# Siwa_PCB.net
KiCad netlist of a schematic drawn in Altium Designer
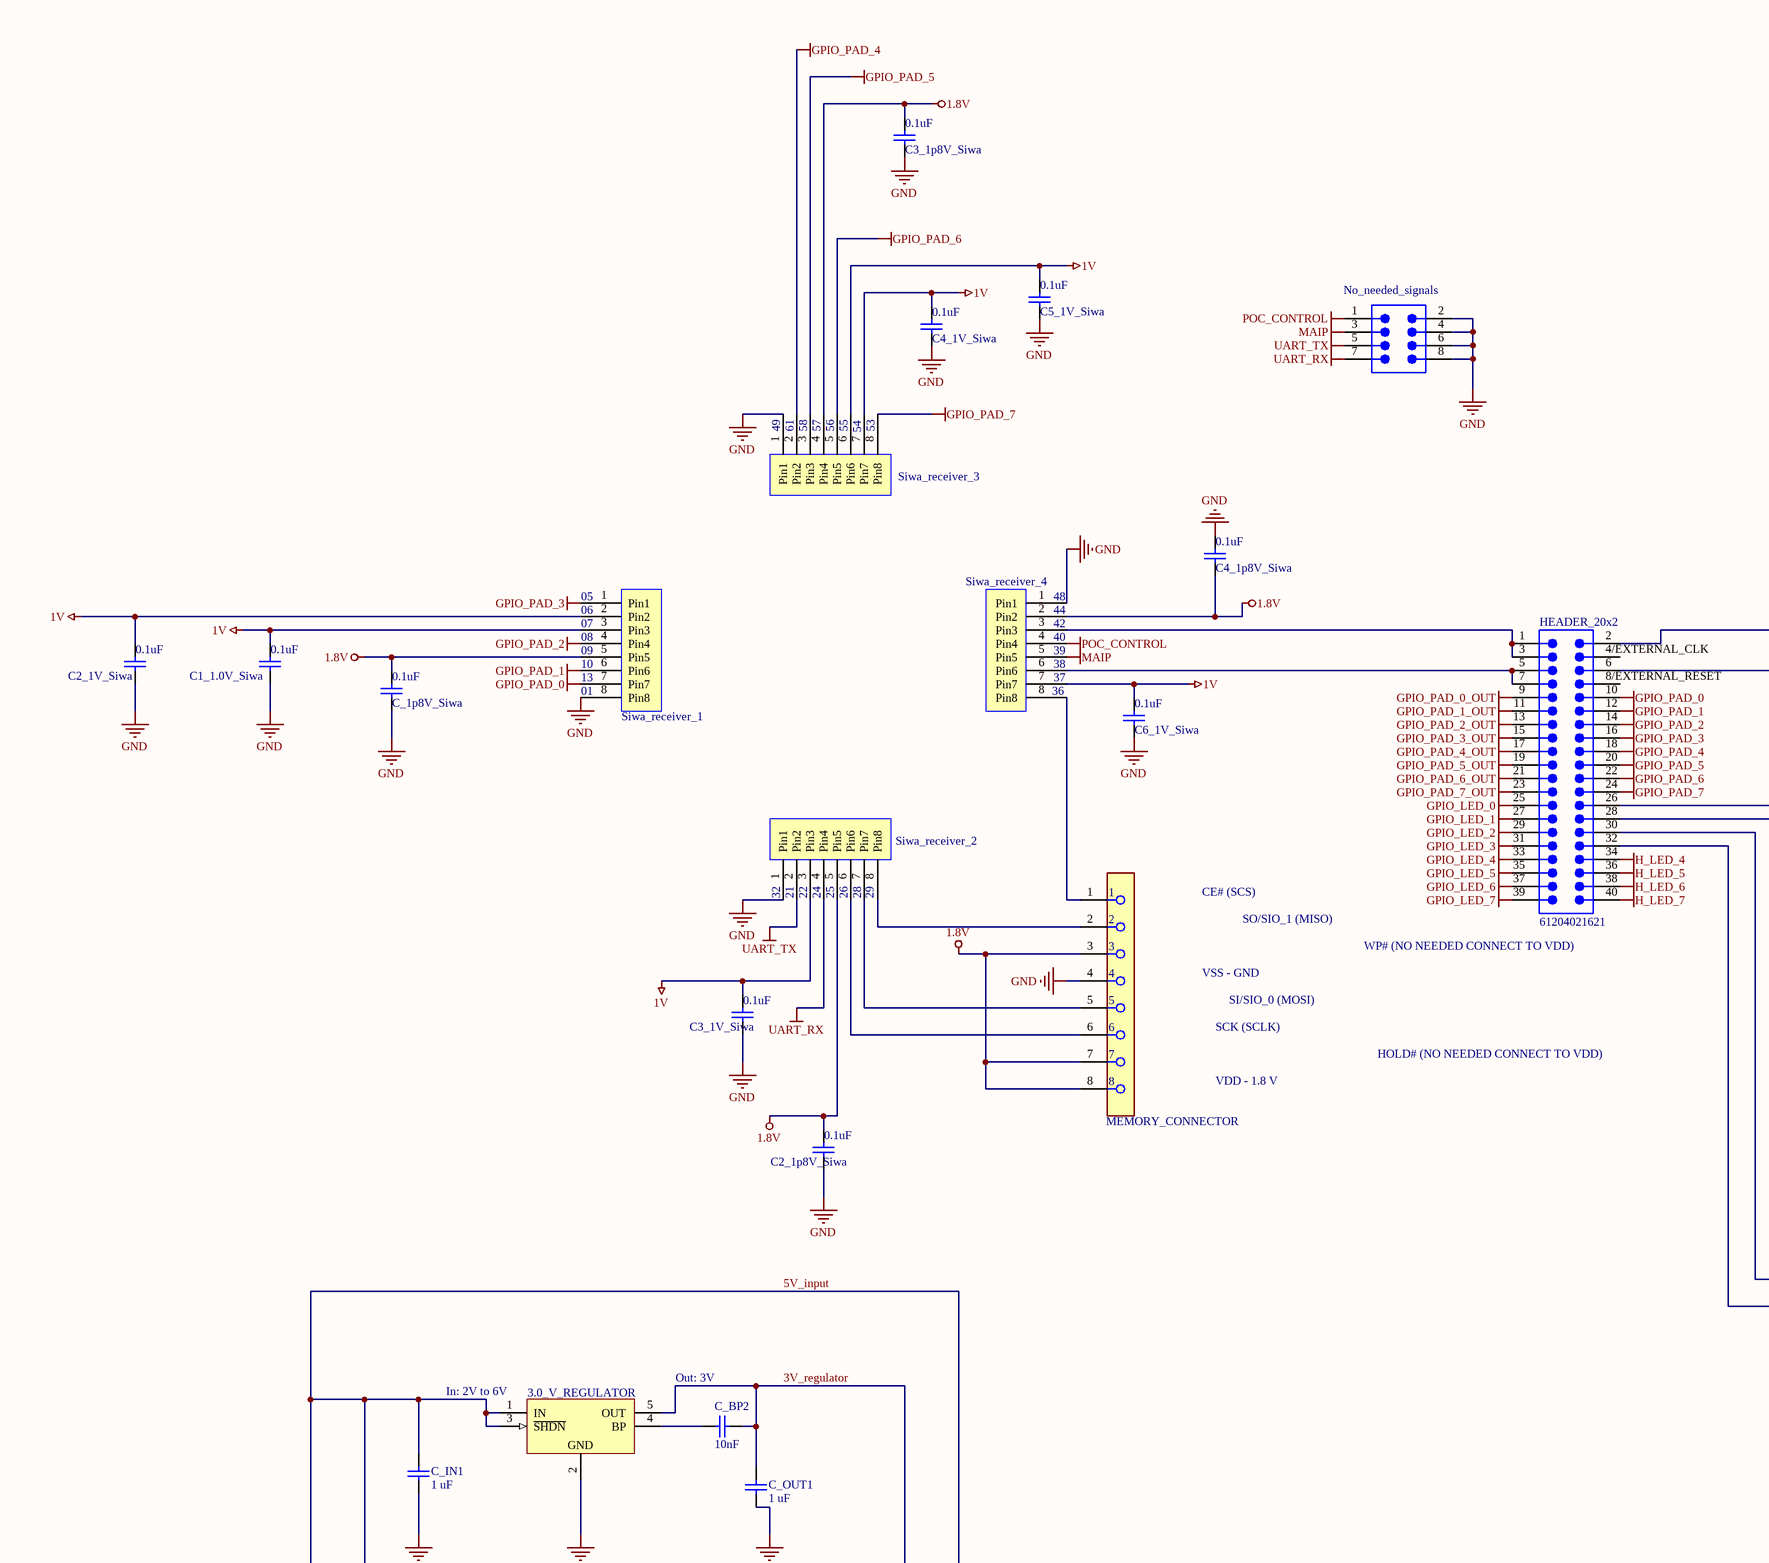
[diagram p0: Siwa_PCB.SchDoc, top left]
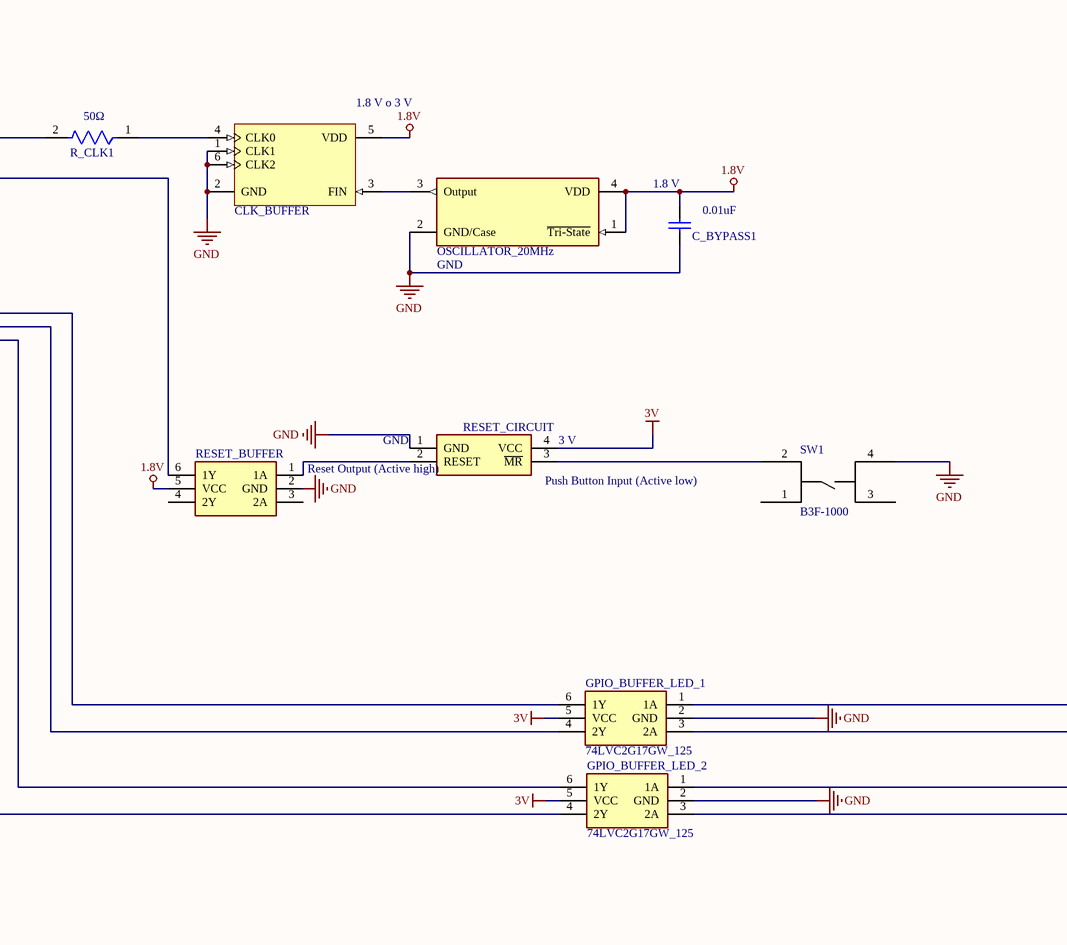
[diagram p1: Siwa_PCB.SchDoc, top right]
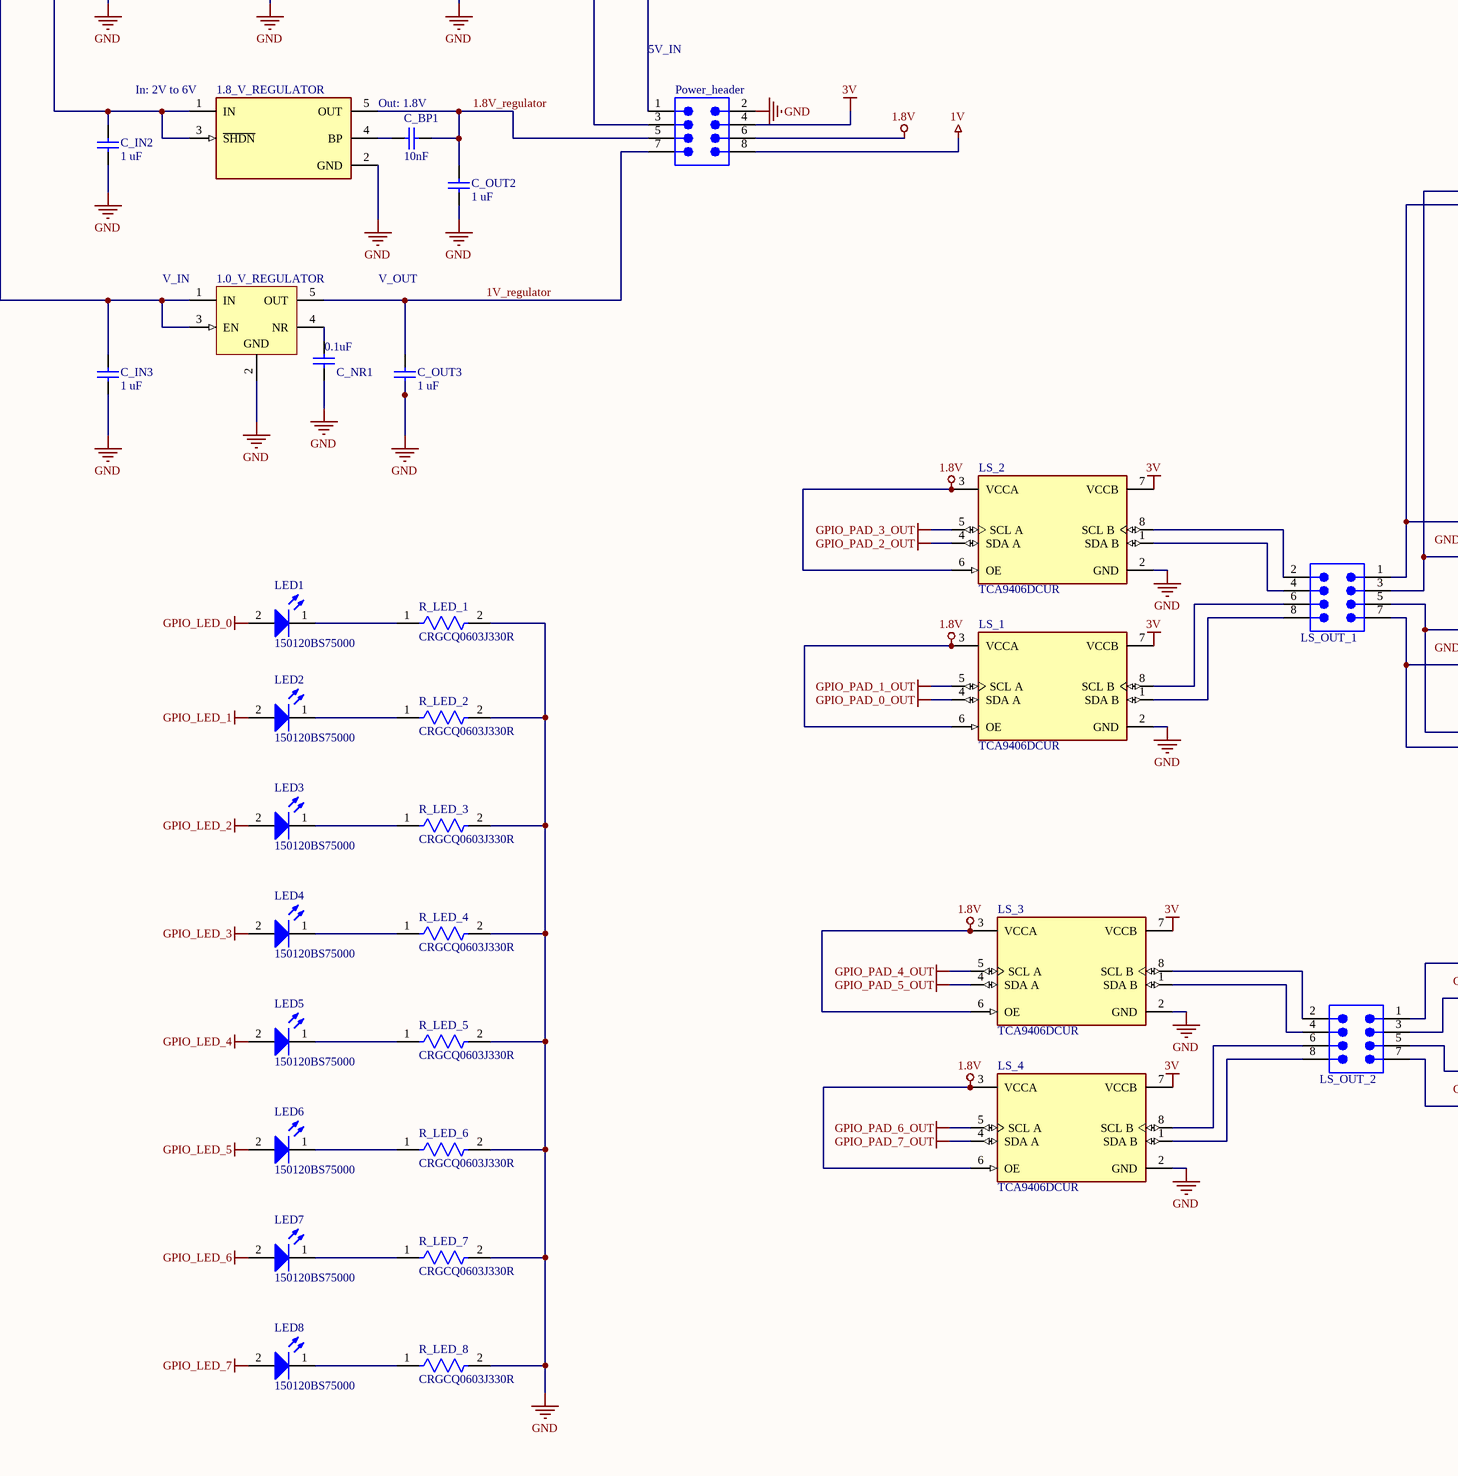
[diagram p2: Siwa_PCB.SchDoc, bottom left]
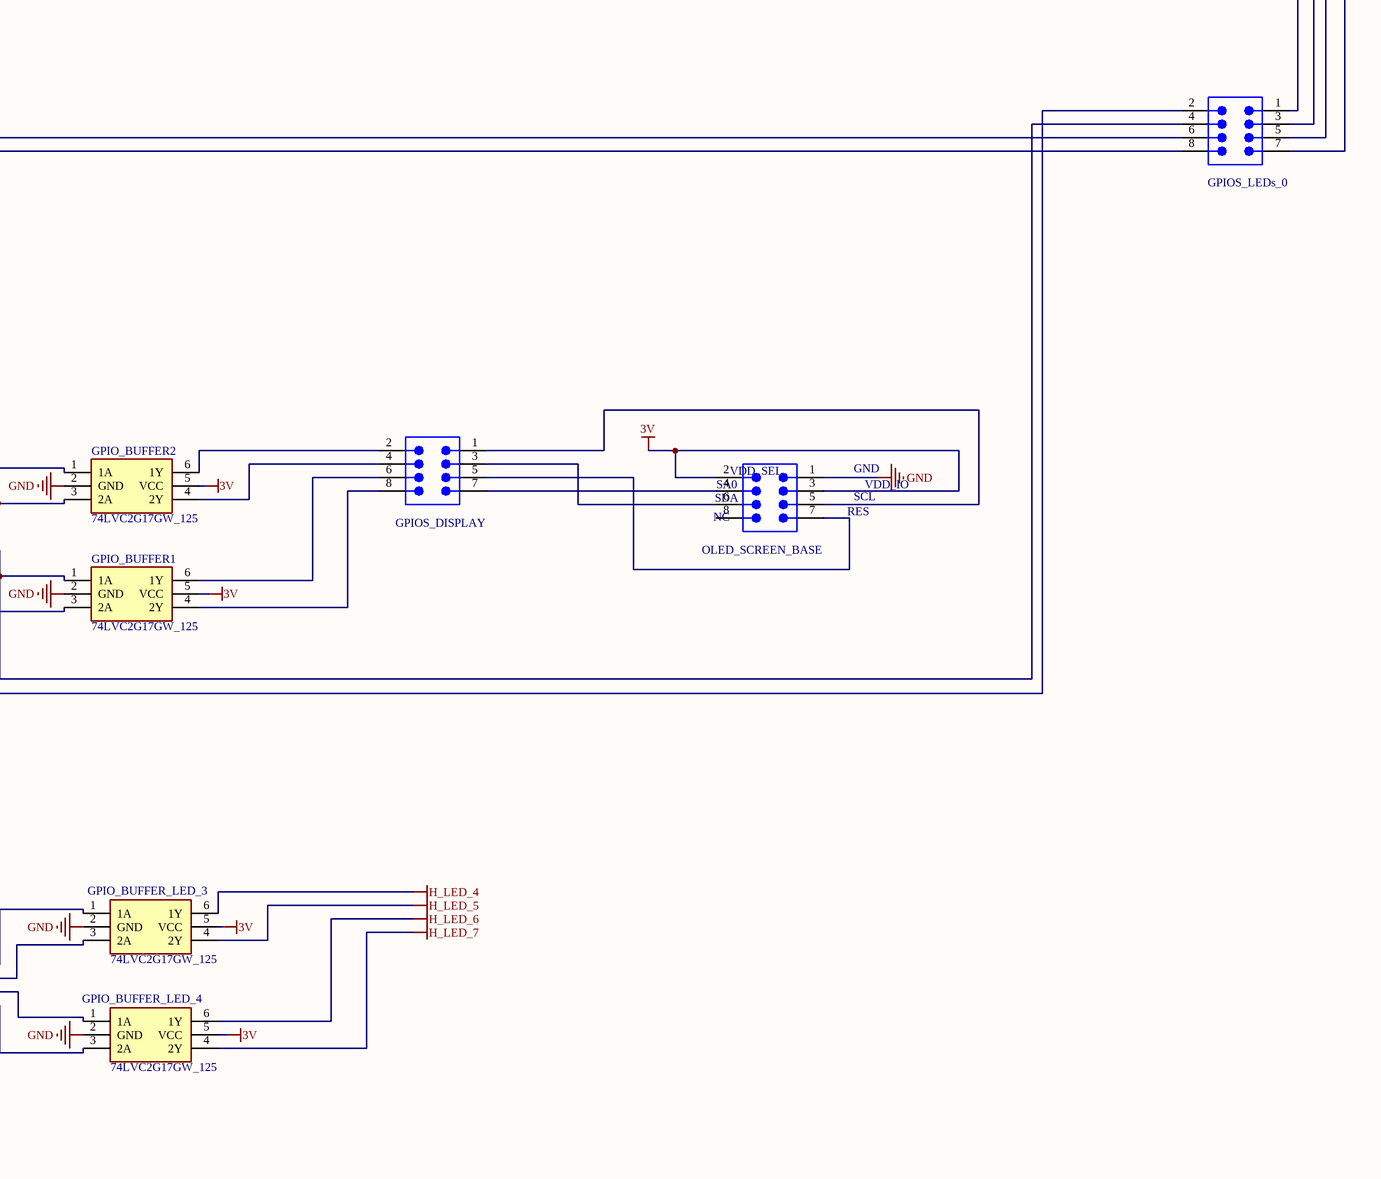
[diagram p3: Siwa_PCB.SchDoc, bottom right]

(export (version "E")
  (design (tool "Eeschema 10.0.6"))
  (components
    (comp (ref "1.0_V_REGULATOR")
      (value "TPS71710DCKT")
      (footprint "DCK0005A_M")
      (fields (field (name "MANUFACTURER") "Texas Instruments"))
      (libsource (lib "Altium Content Vault") (part "TI-TPS79NXX-YYSOT5"))
    )
    (comp (ref "1.8_V_REGULATOR")
      (value "MAX8510EXK18+T")
      (footprint "FP-X5-1-MFG")
      (description "IC REG LINEAR 1.8V 120MA SC70-5")
      (libsource (lib "Altium Content Vault") (part "355d6218c957986cfc1b3588039a240"))
    )
    (comp (ref "3.0_V_REGULATOR")
      (value "MAX8510EXK30+T")
      (footprint "X5-1_N")
      (libsource (lib "Altium Content Vault") (part "MAX-MAX8510-SOT5"))
    )
    (comp (ref "C1_1.0V_Siwa")
      (value "0.1uF")
      (footprint "CAPC1608X92X38NL15T08")
      (fields (field (name "MANUFACTURER") "Vitramon") (field (name "PART NUMBER") "VJ0603Y104KXXAP"))
      (libsource (lib "Altium Content Vault") (part "CAP"))
    )
    (comp (ref "C2_1p8V_Siwa")
      (value "0.1uF")
      (footprint "CAPC1608X92X38NL15T08")
      (fields (field (name "MANUFACTURER") "Vitramon") (field (name "PART NUMBER") "VJ0603Y104KXXAP"))
      (libsource (lib "Altium Content Vault") (part "CAP"))
    )
    (comp (ref "C2_1V_Siwa")
      (value "0.1uF")
      (footprint "CAPC1608X92X38NL15T08")
      (fields (field (name "MANUFACTURER") "Vitramon") (field (name "PART NUMBER") "VJ0603Y104KXXAP"))
      (libsource (lib "Altium Content Vault") (part "CAP"))
    )
    (comp (ref "C3_1p8V_Siwa")
      (value "0.1uF")
      (footprint "CAPC1608X92X38NL15T08")
      (fields (field (name "MANUFACTURER") "Vitramon") (field (name "PART NUMBER") "VJ0603Y104KXXAP"))
      (libsource (lib "Altium Content Vault") (part "CAP"))
    )
    (comp (ref "C3_1V_Siwa")
      (value "0.1uF")
      (footprint "CAPC1608X92X38NL15T08")
      (fields (field (name "MANUFACTURER") "Vitramon") (field (name "PART NUMBER") "VJ0603Y104KXXAP"))
      (libsource (lib "Altium Content Vault") (part "CAP"))
    )
    (comp (ref "C4_1p8V_Siwa")
      (value "0.1uF")
      (footprint "CAPC1608X92X38NL15T08")
      (fields (field (name "MANUFACTURER") "Vitramon") (field (name "PART NUMBER") "VJ0603Y104KXXAP"))
      (libsource (lib "Altium Content Vault") (part "CAP"))
    )
    (comp (ref "C4_1V_Siwa")
      (value "0.1uF")
      (footprint "CAPC1608X92X38NL15T08")
      (fields (field (name "MANUFACTURER") "Vitramon") (field (name "PART NUMBER") "VJ0603Y104KXXAP"))
      (libsource (lib "Altium Content Vault") (part "CAP"))
    )
    (comp (ref "C5_1V_Siwa")
      (value "0.1uF")
      (footprint "CAPC1608X92X38NL15T08")
      (fields (field (name "MANUFACTURER") "Vitramon") (field (name "PART NUMBER") "VJ0603Y104KXXAP"))
      (libsource (lib "Altium Content Vault") (part "CAP"))
    )
    (comp (ref "C6_1V_Siwa")
      (value "0.1uF")
      (footprint "CAPC1608X92X38NL15T08")
      (fields (field (name "MANUFACTURER") "Vitramon") (field (name "PART NUMBER") "VJ0603Y104KXXAP"))
      (libsource (lib "Altium Content Vault") (part "CAP"))
    )
    (comp (ref "CLK_BUFFER")
      (value "PL133-37TI")
      (footprint "FP-SOT23-6LD-PL-1-MFG")
      (libsource (lib "Altium Content Vault") (part "PL133-37TI"))
    )
    (comp (ref "C_1p8V_Siwa")
      (value "0.1uF")
      (footprint "CAPC1608X92X38NL15T08")
      (fields (field (name "MANUFACTURER") "Vitramon") (field (name "PART NUMBER") "VJ0603Y104KXXAP"))
      (libsource (lib "Altium Content Vault") (part "CAP"))
    )
    (comp (ref "C_BP1")
      (value "10nF")
      (footprint "CAPC1608X92X38LL15T08")
      (fields (field (name "MANUFACTURER") "Vitramon") (field (name "PART NUMBER") "VJ0603Y103JXXAC"))
      (libsource (lib "Altium Content Vault") (part "CAP"))
    )
    (comp (ref "C_BP2")
      (value "10nF")
      (footprint "CAPC1608X92X38LL15T08")
      (fields (field (name "MANUFACTURER") "Vitramon") (field (name "PART NUMBER") "VJ0603Y103JXXAC"))
      (libsource (lib "Altium Content Vault") (part "CAP"))
    )
    (comp (ref "C_BYPASS1")
      (value "0.01uF")
      (footprint "CAPC1608X92X38NL15T08")
      (fields (field (name "MANUFACTURER") "Vitramon") (field (name "PART NUMBER") "VJ0603Y103KXAAP"))
      (libsource (lib "Altium Content Vault") (part "CAP"))
    )
    (comp (ref "C_IN1")
      (value "1 uF")
      (footprint "CAPC1608X90X35LL15T15")
      (fields
        (field (name "MANUFACTURER") "AVX Interconnect / Elco")
        (field (name "PART NUMBER") "0603YG105ZAT2A")
      )
      (libsource (lib "Altium Content Vault") (part "CAP"))
    )
    (comp (ref "C_IN2")
      (value "1 uF")
      (footprint "CAPC1608X90X35LL15T15")
      (fields
        (field (name "MANUFACTURER") "AVX Interconnect / Elco")
        (field (name "PART NUMBER") "0603YG105ZAT2A")
      )
      (libsource (lib "Altium Content Vault") (part "CAP"))
    )
    (comp (ref "C_IN3")
      (value "1 uF")
      (footprint "CAPC1608X90X35LL15T15")
      (fields
        (field (name "MANUFACTURER") "AVX Interconnect / Elco")
        (field (name "PART NUMBER") "0603YG105ZAT2A")
      )
      (libsource (lib "Altium Content Vault") (part "CAP"))
    )
    (comp (ref "C_NR1")
      (value "0.1uF")
      (footprint "CAPC1608X92X38NL15T08")
      (fields (field (name "MANUFACTURER") "Vitramon") (field (name "PART NUMBER") "VJ0603Y104KXXAP"))
      (libsource (lib "Altium Content Vault") (part "CAP"))
    )
    (comp (ref "C_OUT1")
      (value "1 uF")
      (footprint "CAPC1608X90X35LL15T15")
      (fields
        (field (name "MANUFACTURER") "AVX Interconnect / Elco")
        (field (name "PART NUMBER") "0603YG105ZAT2A")
      )
      (libsource (lib "Altium Content Vault") (part "CAP"))
    )
    (comp (ref "C_OUT2")
      (value "1 uF")
      (footprint "CAPC1608X90X35LL15T15")
      (fields
        (field (name "MANUFACTURER") "AVX Interconnect / Elco")
        (field (name "PART NUMBER") "0603YG105ZAT2A")
      )
      (libsource (lib "Altium Content Vault") (part "CAP"))
    )
    (comp (ref "C_OUT3")
      (value "1 uF")
      (footprint "CAPC1608X90X35LL15T15")
      (fields
        (field (name "MANUFACTURER") "AVX Interconnect / Elco")
        (field (name "PART NUMBER") "0603YG105ZAT2A")
      )
      (libsource (lib "Altium Content Vault") (part "CAP"))
    )
    (comp (ref "GPIOS_DISPLAY")
      (value "61200821621")
      (footprint "61200821621")
      (description "Wr-bhd; 2.54MM Pitch 8 Way 2 Row Shrouded Straight Pcb Header, Surface Mount")
      (libsource (lib "Altium Content Vault") (part "Header_Male_2R_08P"))
    )
    (comp (ref "GPIOS_LEDs_0")
      (value "61200821621")
      (footprint "61200821621")
      (description "Wr-bhd; 2.54MM Pitch 8 Way 2 Row Shrouded Straight Pcb Header, Surface Mount")
      (libsource (lib "Altium Content Vault") (part "Header_Male_2R_08P"))
    )
    (comp (ref "GPIO_BUFFER1")
      (value "74LVC2G17GW_125")
      (footprint "SOT65P210X110-6N")
      (fields
        (field (name "MANUFACTURER_PART_NUMBER") "74LVC2G17GW,125")
        (field (name "MOUSER PART NUMBER") "771-LVC2G17GW125")
      )
      (libsource (lib "") (part "74LVC2G17GW_125_1"))
    )
    (comp (ref "GPIO_BUFFER2")
      (value "74LVC2G17GW_125")
      (footprint "SOT65P210X110-6N")
      (fields
        (field (name "MANUFACTURER_PART_NUMBER") "74LVC2G17GW,125")
        (field (name "MOUSER PART NUMBER") "771-LVC2G17GW125")
      )
      (libsource (lib "") (part "74LVC2G17GW_125_1"))
    )
    (comp (ref "GPIO_BUFFER_LED_1")
      (value "74LVC2G17GW_125")
      (footprint "SOT65P210X110-6N")
      (fields
        (field (name "MANUFACTURER_PART_NUMBER") "74LVC2G17GW,125")
        (field (name "MOUSER PART NUMBER") "771-LVC2G17GW125")
      )
      (libsource (lib "74LVC2G17GW_125") (part "74LVC2G17GW_125"))
    )
    (comp (ref "GPIO_BUFFER_LED_2")
      (value "74LVC2G17GW_125")
      (footprint "SOT65P210X110-6N")
      (fields
        (field (name "MANUFACTURER_PART_NUMBER") "74LVC2G17GW,125")
        (field (name "MOUSER PART NUMBER") "771-LVC2G17GW125")
      )
      (libsource (lib "74LVC2G17GW_125") (part "74LVC2G17GW_125"))
    )
    (comp (ref "GPIO_BUFFER_LED_3")
      (value "74LVC2G17GW_125")
      (footprint "SOT65P210X110-6N")
      (fields
        (field (name "MANUFACTURER_PART_NUMBER") "74LVC2G17GW,125")
        (field (name "MOUSER PART NUMBER") "771-LVC2G17GW125")
      )
      (libsource (lib "") (part "74LVC2G17GW_125_1"))
    )
    (comp (ref "GPIO_BUFFER_LED_4")
      (value "74LVC2G17GW_125")
      (footprint "SOT65P210X110-6N")
      (fields
        (field (name "MANUFACTURER_PART_NUMBER") "74LVC2G17GW,125")
        (field (name "MOUSER PART NUMBER") "771-LVC2G17GW125")
      )
      (libsource (lib "") (part "74LVC2G17GW_125_1"))
    )
    (comp (ref "HEADER_20x2")
      (value "61204021621")
      (footprint "61204021621")
      (description "WR-BHD Straight Male, Box Header, Through Hole, 2 Rows, 40 Contacts, 2.54mm Pitch")
      (libsource (lib "Altium Content Vault") (part "Header_Male_2R_40P"))
    )
    (comp (ref "LED1")
      (value "150120BS75000")
      (footprint "WL-SMCW_1206_150120xx75000")
      (description "WL-SMCW SMT Mono-Color Chip LED Waterclear")
      (libsource (lib "Altium Content Vault") (part "LED_Blue_2A-1K"))
    )
    (comp (ref "LED2")
      (value "150120BS75000")
      (footprint "WL-SMCW_1206_150120xx75000")
      (description "WL-SMCW SMT Mono-Color Chip LED Waterclear")
      (libsource (lib "Altium Content Vault") (part "LED_Blue_2A-1K"))
    )
    (comp (ref "LED3")
      (value "150120BS75000")
      (footprint "WL-SMCW_1206_150120xx75000")
      (description "WL-SMCW SMT Mono-Color Chip LED Waterclear")
      (libsource (lib "Altium Content Vault") (part "LED_Blue_2A-1K"))
    )
    (comp (ref "LED4")
      (value "150120BS75000")
      (footprint "WL-SMCW_1206_150120xx75000")
      (description "WL-SMCW SMT Mono-Color Chip LED Waterclear")
      (libsource (lib "Altium Content Vault") (part "LED_Blue_2A-1K"))
    )
    (comp (ref "LED5")
      (value "150120BS75000")
      (footprint "WL-SMCW_1206_150120xx75000")
      (description "WL-SMCW SMT Mono-Color Chip LED Waterclear")
      (libsource (lib "Altium Content Vault") (part "LED_Blue_2A-1K"))
    )
    (comp (ref "LED6")
      (value "150120BS75000")
      (footprint "WL-SMCW_1206_150120xx75000")
      (description "WL-SMCW SMT Mono-Color Chip LED Waterclear")
      (libsource (lib "Altium Content Vault") (part "LED_Blue_2A-1K"))
    )
    (comp (ref "LED7")
      (value "150120BS75000")
      (footprint "WL-SMCW_1206_150120xx75000")
      (description "WL-SMCW SMT Mono-Color Chip LED Waterclear")
      (libsource (lib "Altium Content Vault") (part "LED_Blue_2A-1K"))
    )
    (comp (ref "LED8")
      (value "150120BS75000")
      (footprint "WL-SMCW_1206_150120xx75000")
      (description "WL-SMCW SMT Mono-Color Chip LED Waterclear")
      (libsource (lib "Altium Content Vault") (part "LED_Blue_2A-1K"))
    )
    (comp (ref "LS_1")
      (value "TCA9406DCUR")
      (footprint "FP-DCU0008A-IPC_B")
      (description "IC TRNSLTR BIDIRECTIONAL US8")
      (libsource (lib "Altium Content Vault") (part "2e2e7ab415e70eec0fdfb76e593e2e7"))
    )
    (comp (ref "LS_2")
      (value "TCA9406DCUR")
      (footprint "FP-DCU0008A-IPC_B")
      (description "IC TRNSLTR BIDIRECTIONAL US8")
      (libsource (lib "Altium Content Vault") (part "2e2e7ab415e70eec0fdfb76e593e2e7"))
    )
    (comp (ref "LS_3")
      (value "TCA9406DCUR")
      (footprint "FP-DCU0008A-IPC_B")
      (description "IC TRNSLTR BIDIRECTIONAL US8")
      (libsource (lib "Altium Content Vault") (part "2e2e7ab415e70eec0fdfb76e593e2e7"))
    )
    (comp (ref "LS_4")
      (value "TCA9406DCUR")
      (footprint "FP-DCU0008A-IPC_B")
      (description "IC TRNSLTR BIDIRECTIONAL US8")
      (libsource (lib "Altium Content Vault") (part "2e2e7ab415e70eec0fdfb76e593e2e7"))
    )
    (comp (ref "LS_OUT_1")
      (value "61200821621")
      (footprint "61200821621")
      (description "Wr-bhd; 2.54MM Pitch 8 Way 2 Row Shrouded Straight Pcb Header, Surface Mount")
      (libsource (lib "Altium Content Vault") (part "Header_Male_2R_08P"))
    )
    (comp (ref "LS_OUT_2")
      (value "61200821621")
      (footprint "61200821621")
      (description "Wr-bhd; 2.54MM Pitch 8 Way 2 Row Shrouded Straight Pcb Header, Surface Mount")
      (libsource (lib "Altium Content Vault") (part "Header_Male_2R_08P"))
    )
    (comp (ref "MEMORY_CONNECTOR")
      (value "DIP8_base")
      (footprint "FP-1-2199298-2-MFG")
      (description "CONN IC DIP SOCKET 8POS TIN")
      (libsource (lib "Altium Content Vault") (part "b0a0b555dd3abf3683e7c330df25cc4"))
    )
    (comp (ref "No_needed_signals")
      (value "61200821621")
      (footprint "61200821621")
      (description "Wr-bhd; 2.54MM Pitch 8 Way 2 Row Shrouded Straight Pcb Header, Surface Mount")
      (libsource (lib "Altium Content Vault") (part "Header_Male_2R_08P"))
    )
    (comp (ref "OLED_SCREEN_BASE")
      (value "61200821621")
      (footprint "61200821621")
      (description "Wr-bhd; 2.54MM Pitch 8 Way 2 Row Shrouded Straight Pcb Header, Surface Mount")
      (libsource (lib "Altium Content Vault") (part "Header_Male_2R_08P"))
    )
    (comp (ref "OSCILLATOR_20MHz")
      (value "ASE3-20.000MHZ-KT")
      (footprint "FP-ASE3-MFG")
      (description "XTAL OSC XO 20.0000MHZ CMOS SMD")
      (libsource (lib "Altium Content Vault") (part "37c4c26fe5ae6223af2046a137c0b30"))
    )
    (comp (ref "Power_header")
      (value "61200821621")
      (footprint "61200821621")
      (description "Wr-bhd; 2.54MM Pitch 8 Way 2 Row Shrouded Straight Pcb Header, Surface Mount")
      (libsource (lib "Altium Content Vault") (part "Header_Male_2R_08P"))
    )
    (comp (ref "RESET_BUFFER")
      (value "74LVC2G17GW_125")
      (footprint "SOT65P210X110-6N")
      (fields
        (field (name "MANUFACTURER_PART_NUMBER") "74LVC2G17GW,125")
        (field (name "MOUSER PART NUMBER") "771-LVC2G17GW125")
      )
      (libsource (lib "74LVC2G17GW_125") (part "74LVC2G17GW_125"))
    )
    (comp (ref "RESET_CIRCUIT")
      (value "APX812-29UG-7")
      (footprint "APX81229UG7")
      (description "Supervisor Push-Pull, Totem Pole 1 Channel SOT-143 , 2.93V , 140ms , -40C ~ 85C (TA)")
      (fields (field (name "MOUSER PART NUMBER") "621-APX812-29UG-7"))
      (libsource (lib "APX812-29UG-7") (part "APX812-29UG-7"))
    )
    (comp (ref "R_CLK1")
      (value "50Ω")
      (footprint "FP-D12-CRCW0805-MFG")
      (description "CRCW080550R0FKTA Res Thick Film 0805 50 Ohm 1% 0.125W(1/8W) ±100ppm/C Pad SMD Automotive T/R")
      (fields (field (name "TOLERANCE") "1%"))
      (libsource (lib "Altium Content Vault") (part "1029c3af85768c4190bb7ad29bc67b5"))
    )
    (comp (ref "R_LED_1")
      (value "CRGCQ0603J330R")
      (footprint "FP-CRGCQ0603-IPC_C")
      (description "CRGCQ 0603 330R 5%")
      (fields
        (field (name "OCTOPART") "https://octopart.com/crgcq0603j330r-te+connectivity-91018118")
        (field (name "MANUFACTURER") "TE Connectivity")
      )
      (libsource (lib "Altium Content Vault") (part "1029c3af85768c4190bb7ad29bc67b5"))
    )
    (comp (ref "R_LED_2")
      (value "CRGCQ0603J330R")
      (footprint "FP-CRGCQ0603-IPC_C")
      (description "CRGCQ 0603 330R 5%")
      (fields
        (field (name "OCTOPART") "https://octopart.com/crgcq0603j330r-te+connectivity-91018118")
        (field (name "MANUFACTURER") "TE Connectivity")
      )
      (libsource (lib "Altium Content Vault") (part "1029c3af85768c4190bb7ad29bc67b5"))
    )
    (comp (ref "R_LED_3")
      (value "CRGCQ0603J330R")
      (footprint "FP-CRGCQ0603-IPC_C")
      (description "CRGCQ 0603 330R 5%")
      (fields
        (field (name "OCTOPART") "https://octopart.com/crgcq0603j330r-te+connectivity-91018118")
        (field (name "MANUFACTURER") "TE Connectivity")
      )
      (libsource (lib "Altium Content Vault") (part "1029c3af85768c4190bb7ad29bc67b5"))
    )
    (comp (ref "R_LED_4")
      (value "CRGCQ0603J330R")
      (footprint "FP-CRGCQ0603-IPC_C")
      (description "CRGCQ 0603 330R 5%")
      (fields
        (field (name "OCTOPART") "https://octopart.com/crgcq0603j330r-te+connectivity-91018118")
        (field (name "MANUFACTURER") "TE Connectivity")
      )
      (libsource (lib "Altium Content Vault") (part "1029c3af85768c4190bb7ad29bc67b5"))
    )
    (comp (ref "R_LED_5")
      (value "CRGCQ0603J330R")
      (footprint "FP-CRGCQ0603-IPC_C")
      (description "CRGCQ 0603 330R 5%")
      (fields
        (field (name "OCTOPART") "https://octopart.com/crgcq0603j330r-te+connectivity-91018118")
        (field (name "MANUFACTURER") "TE Connectivity")
      )
      (libsource (lib "Altium Content Vault") (part "1029c3af85768c4190bb7ad29bc67b5"))
    )
    (comp (ref "R_LED_6")
      (value "CRGCQ0603J330R")
      (footprint "FP-CRGCQ0603-IPC_C")
      (description "CRGCQ 0603 330R 5%")
      (fields
        (field (name "OCTOPART") "https://octopart.com/crgcq0603j330r-te+connectivity-91018118")
        (field (name "MANUFACTURER") "TE Connectivity")
      )
      (libsource (lib "Altium Content Vault") (part "1029c3af85768c4190bb7ad29bc67b5"))
    )
    (comp (ref "R_LED_7")
      (value "CRGCQ0603J330R")
      (footprint "FP-CRGCQ0603-IPC_C")
      (description "CRGCQ 0603 330R 5%")
      (fields
        (field (name "OCTOPART") "https://octopart.com/crgcq0603j330r-te+connectivity-91018118")
        (field (name "MANUFACTURER") "TE Connectivity")
      )
      (libsource (lib "Altium Content Vault") (part "1029c3af85768c4190bb7ad29bc67b5"))
    )
    (comp (ref "R_LED_8")
      (value "CRGCQ0603J330R")
      (footprint "FP-CRGCQ0603-IPC_C")
      (description "CRGCQ 0603 330R 5%")
      (fields
        (field (name "OCTOPART") "https://octopart.com/crgcq0603j330r-te+connectivity-91018118")
        (field (name "MANUFACTURER") "TE Connectivity")
      )
      (libsource (lib "Altium Content Vault") (part "1029c3af85768c4190bb7ad29bc67b5"))
    )
    (comp (ref "Siwa_receiver_1")
      (value "HEADER 8P 2.54mm")
      (footprint "PPTC081LFBN-RC")
      (libsource (lib "") (part "PPTC081LFBN-RC_2"))
    )
    (comp (ref "Siwa_receiver_2")
      (value "HEADER 8P 2.54mm")
      (footprint "PPTC081LFBN-RC")
      (libsource (lib "PPTC081LFBN-RC") (part "PPTC081LFBN-RC"))
    )
    (comp (ref "Siwa_receiver_3")
      (value "HEADER 8P 2.54mm")
      (footprint "PPTC081LFBN-RC")
      (libsource (lib "") (part "PPTC081LFBN-RC_3"))
    )
    (comp (ref "Siwa_receiver_4")
      (value "HEADER 8P 2.54mm")
      (footprint "PPTC081LFBN-RC")
      (libsource (lib "") (part "PPTC081LFBN-RC_1"))
    )
    (comp (ref "SW1")
      (value "B3F-1000")
      (footprint "PCBComponent_1")
      (libsource (lib "B3F-1000S") (part "B3F-1000S"))
    )
  )
  (nets
    (net (code "1") (name "/1.8V_regulator") (class "Default")
      (node (ref "1.8_V_REGULATOR") (pin "5") (pinfunction "OUT_5") (pintype "power_in"))
      (node (ref "C_BP1") (pin "2") (pinfunction "2_2") (pintype "passive"))
      (node (ref "C_OUT2") (pin "2") (pinfunction "2_2") (pintype "passive"))
      (node (ref "Power_header") (pin "5") (pinfunction "5_5") (pintype "passive"))
    )
    (net (code "2") (name "/1V_regulator") (class "Default")
      (node (ref "1.0_V_REGULATOR") (pin "5") (pinfunction "OUT_5") (pintype "power_in"))
      (node (ref "C_OUT3") (pin "2") (pinfunction "2_2") (pintype "passive"))
      (node (ref "Power_header") (pin "7") (pinfunction "7_7") (pintype "passive"))
    )
    (net (code "3") (name "/3V_regulator") (class "Default")
      (node (ref "3.0_V_REGULATOR") (pin "5") (pinfunction "OUT_5") (pintype "power_in"))
      (node (ref "C_BP2") (pin "2") (pinfunction "2_2") (pintype "passive"))
      (node (ref "C_OUT1") (pin "2") (pinfunction "2_2") (pintype "passive"))
      (node (ref "Power_header") (pin "3") (pinfunction "3_3") (pintype "passive"))
    )
    (net (code "4") (name "/5V_input") (class "Default")
      (node (ref "1.0_V_REGULATOR") (pin "1") (pinfunction "IN_1") (pintype "power_in"))
      (node (ref "1.0_V_REGULATOR") (pin "3") (pinfunction "EN_3") (pintype "input"))
      (node (ref "1.8_V_REGULATOR") (pin "1") (pinfunction "IN_1") (pintype "power_in"))
      (node (ref "1.8_V_REGULATOR") (pin "3") (pinfunction "~{SHDN}_3") (pintype "input"))
      (node (ref "3.0_V_REGULATOR") (pin "1") (pinfunction "IN_1") (pintype "power_in"))
      (node (ref "3.0_V_REGULATOR") (pin "3") (pinfunction "~{SHDN}_3") (pintype "input"))
      (node (ref "C_IN1") (pin "2") (pinfunction "2_2") (pintype "passive"))
      (node (ref "C_IN2") (pin "2") (pinfunction "2_2") (pintype "passive"))
      (node (ref "C_IN3") (pin "2") (pinfunction "2_2") (pintype "passive"))
      (node (ref "Power_header") (pin "1") (pinfunction "1_1") (pintype "passive"))
    )
    (net (code "5") (name "1.8V") (class "Default")
      (node (ref "C2_1p8V_Siwa") (pin "2") (pinfunction "2_2") (pintype "passive"))
      (node (ref "C3_1p8V_Siwa") (pin "2") (pinfunction "2_2") (pintype "passive"))
      (node (ref "C4_1p8V_Siwa") (pin "1") (pinfunction "1_1") (pintype "passive"))
      (node (ref "CLK_BUFFER") (pin "5") (pinfunction "VDD_5") (pintype "power_in"))
      (node (ref "C_1p8V_Siwa") (pin "2") (pinfunction "2_2") (pintype "passive"))
      (node (ref "C_BYPASS1") (pin "2") (pinfunction "2_2") (pintype "passive"))
      (node (ref "LS_1") (pin "3") (pinfunction "VCCA_3") (pintype "power_in"))
      (node (ref "LS_1") (pin "6") (pinfunction "OE_6") (pintype "input"))
      (node (ref "LS_2") (pin "3") (pinfunction "VCCA_3") (pintype "power_in"))
      (node (ref "LS_2") (pin "6") (pinfunction "OE_6") (pintype "input"))
      (node (ref "LS_3") (pin "3") (pinfunction "VCCA_3") (pintype "power_in"))
      (node (ref "LS_3") (pin "6") (pinfunction "OE_6") (pintype "input"))
      (node (ref "LS_4") (pin "3") (pinfunction "VCCA_3") (pintype "power_in"))
      (node (ref "LS_4") (pin "6") (pinfunction "OE_6") (pintype "input"))
      (node (ref "MEMORY_CONNECTOR") (pin "3") (pinfunction "3_3") (pintype "passive"))
      (node (ref "MEMORY_CONNECTOR") (pin "7") (pinfunction "7_7") (pintype "passive"))
      (node (ref "MEMORY_CONNECTOR") (pin "8") (pinfunction "8_8") (pintype "passive"))
      (node (ref "OSCILLATOR_20MHz") (pin "1") (pinfunction "~{Tri-State}_1") (pintype "input"))
      (node (ref "OSCILLATOR_20MHz") (pin "4") (pinfunction "VDD_4") (pintype "power_in"))
      (node (ref "Power_header") (pin "6") (pinfunction "6_6") (pintype "passive"))
      (node (ref "RESET_BUFFER") (pin "5") (pinfunction "VCC_5") (pintype "passive"))
      (node (ref "Siwa_receiver_1") (pin "5") (pinfunction "Pin5_5") (pintype "passive"))
      (node (ref "Siwa_receiver_2") (pin "5") (pinfunction "Pin5_5") (pintype "passive"))
      (node (ref "Siwa_receiver_3") (pin "4") (pinfunction "Pin4_4") (pintype "passive"))
      (node (ref "Siwa_receiver_4") (pin "2") (pinfunction "Pin2_2") (pintype "passive"))
    )
    (net (code "6") (name "1V") (class "Default")
      (node (ref "C1_1.0V_Siwa") (pin "2") (pinfunction "2_2") (pintype "passive"))
      (node (ref "C2_1V_Siwa") (pin "2") (pinfunction "2_2") (pintype "passive"))
      (node (ref "C3_1V_Siwa") (pin "2") (pinfunction "2_2") (pintype "passive"))
      (node (ref "C4_1V_Siwa") (pin "2") (pinfunction "2_2") (pintype "passive"))
      (node (ref "C5_1V_Siwa") (pin "2") (pinfunction "2_2") (pintype "passive"))
      (node (ref "C6_1V_Siwa") (pin "2") (pinfunction "2_2") (pintype "passive"))
      (node (ref "Power_header") (pin "8") (pinfunction "8_8") (pintype "passive"))
      (node (ref "Siwa_receiver_1") (pin "2") (pinfunction "Pin2_2") (pintype "passive"))
      (node (ref "Siwa_receiver_1") (pin "3") (pinfunction "Pin3_3") (pintype "passive"))
      (node (ref "Siwa_receiver_2") (pin "3") (pinfunction "Pin3_3") (pintype "passive"))
      (node (ref "Siwa_receiver_3") (pin "6") (pinfunction "Pin6_6") (pintype "passive"))
      (node (ref "Siwa_receiver_3") (pin "7") (pinfunction "Pin7_7") (pintype "passive"))
      (node (ref "Siwa_receiver_4") (pin "7") (pinfunction "Pin7_7") (pintype "passive"))
    )
    (net (code "7") (name "3V") (class "Default")
      (node (ref "GPIO_BUFFER1") (pin "5") (pinfunction "VCC_5") (pintype "passive"))
      (node (ref "GPIO_BUFFER2") (pin "5") (pinfunction "VCC_5") (pintype "passive"))
      (node (ref "GPIO_BUFFER_LED_1") (pin "5") (pinfunction "VCC_5") (pintype "passive"))
      (node (ref "GPIO_BUFFER_LED_2") (pin "5") (pinfunction "VCC_5") (pintype "passive"))
      (node (ref "GPIO_BUFFER_LED_3") (pin "5") (pinfunction "VCC_5") (pintype "passive"))
      (node (ref "GPIO_BUFFER_LED_4") (pin "5") (pinfunction "VCC_5") (pintype "passive"))
      (node (ref "LS_1") (pin "7") (pinfunction "VCCB_7") (pintype "power_in"))
      (node (ref "LS_2") (pin "7") (pinfunction "VCCB_7") (pintype "power_in"))
      (node (ref "LS_3") (pin "7") (pinfunction "VCCB_7") (pintype "power_in"))
      (node (ref "LS_4") (pin "7") (pinfunction "VCCB_7") (pintype "power_in"))
      (node (ref "OLED_SCREEN_BASE") (pin "2") (pinfunction "2_2") (pintype "passive"))
      (node (ref "OLED_SCREEN_BASE") (pin "3") (pinfunction "3_3") (pintype "passive"))
      (node (ref "Power_header") (pin "4") (pinfunction "4_4") (pintype "passive"))
      (node (ref "RESET_CIRCUIT") (pin "4") (pinfunction "VCC_4") (pintype "passive"))
    )
    (net (code "8") (name "GND") (class "Default")
      (node (ref "1.0_V_REGULATOR") (pin "2") (pinfunction "GND_2") (pintype "power_in"))
      (node (ref "1.8_V_REGULATOR") (pin "2") (pinfunction "GND_2") (pintype "power_in"))
      (node (ref "3.0_V_REGULATOR") (pin "2") (pinfunction "GND_2") (pintype "power_in"))
      (node (ref "C1_1.0V_Siwa") (pin "1") (pinfunction "1_1") (pintype "passive"))
      (node (ref "C2_1V_Siwa") (pin "1") (pinfunction "1_1") (pintype "passive"))
      (node (ref "C2_1p8V_Siwa") (pin "1") (pinfunction "1_1") (pintype "passive"))
      (node (ref "C3_1V_Siwa") (pin "1") (pinfunction "1_1") (pintype "passive"))
      (node (ref "C3_1p8V_Siwa") (pin "1") (pinfunction "1_1") (pintype "passive"))
      (node (ref "C4_1V_Siwa") (pin "1") (pinfunction "1_1") (pintype "passive"))
      (node (ref "C4_1p8V_Siwa") (pin "2") (pinfunction "2_2") (pintype "passive"))
      (node (ref "C5_1V_Siwa") (pin "1") (pinfunction "1_1") (pintype "passive"))
      (node (ref "C6_1V_Siwa") (pin "1") (pinfunction "1_1") (pintype "passive"))
      (node (ref "CLK_BUFFER") (pin "1") (pinfunction "CLK1_1") (pintype "input"))
      (node (ref "CLK_BUFFER") (pin "2") (pinfunction "GND_2") (pintype "power_in"))
      (node (ref "CLK_BUFFER") (pin "6") (pinfunction "CLK2_6") (pintype "input"))
      (node (ref "C_1p8V_Siwa") (pin "1") (pinfunction "1_1") (pintype "passive"))
      (node (ref "C_BYPASS1") (pin "1") (pinfunction "1_1") (pintype "passive"))
      (node (ref "C_IN1") (pin "1") (pinfunction "1_1") (pintype "passive"))
      (node (ref "C_IN2") (pin "1") (pinfunction "1_1") (pintype "passive"))
      (node (ref "C_IN3") (pin "1") (pinfunction "1_1") (pintype "passive"))
      (node (ref "C_NR1") (pin "1") (pinfunction "1_1") (pintype "passive"))
      (node (ref "C_OUT1") (pin "1") (pinfunction "1_1") (pintype "passive"))
      (node (ref "C_OUT2") (pin "1") (pinfunction "1_1") (pintype "passive"))
      (node (ref "C_OUT3") (pin "1") (pinfunction "1_1") (pintype "passive"))
      (node (ref "GPIO_BUFFER1") (pin "2") (pinfunction "GND_2") (pintype "passive"))
      (node (ref "GPIO_BUFFER2") (pin "2") (pinfunction "GND_2") (pintype "passive"))
      (node (ref "GPIO_BUFFER_LED_1") (pin "2") (pinfunction "GND_2") (pintype "passive"))
      (node (ref "GPIO_BUFFER_LED_2") (pin "2") (pinfunction "GND_2") (pintype "passive"))
      (node (ref "GPIO_BUFFER_LED_3") (pin "2") (pinfunction "GND_2") (pintype "passive"))
      (node (ref "GPIO_BUFFER_LED_4") (pin "2") (pinfunction "GND_2") (pintype "passive"))
      (node (ref "LS_1") (pin "2") (pinfunction "GND_2") (pintype "power_in"))
      (node (ref "LS_2") (pin "2") (pinfunction "GND_2") (pintype "power_in"))
      (node (ref "LS_3") (pin "2") (pinfunction "GND_2") (pintype "power_in"))
      (node (ref "LS_4") (pin "2") (pinfunction "GND_2") (pintype "power_in"))
      (node (ref "MEMORY_CONNECTOR") (pin "4") (pinfunction "4_4") (pintype "passive"))
      (node (ref "No_needed_signals") (pin "2") (pinfunction "2_2") (pintype "passive"))
      (node (ref "No_needed_signals") (pin "4") (pinfunction "4_4") (pintype "passive"))
      (node (ref "No_needed_signals") (pin "6") (pinfunction "6_6") (pintype "passive"))
      (node (ref "No_needed_signals") (pin "8") (pinfunction "8_8") (pintype "passive"))
      (node (ref "OLED_SCREEN_BASE") (pin "1") (pinfunction "1_1") (pintype "passive"))
      (node (ref "OSCILLATOR_20MHz") (pin "2") (pinfunction "GND/Case_2") (pintype "power_in"))
      (node (ref "Power_header") (pin "2") (pinfunction "2_2") (pintype "passive"))
      (node (ref "RESET_BUFFER") (pin "2") (pinfunction "GND_2") (pintype "passive"))
      (node (ref "RESET_CIRCUIT") (pin "1") (pinfunction "GND_1") (pintype "passive"))
      (node (ref "R_LED_1") (pin "2") (pinfunction "2_2") (pintype "passive"))
      (node (ref "R_LED_2") (pin "2") (pinfunction "2_2") (pintype "passive"))
      (node (ref "R_LED_3") (pin "2") (pinfunction "2_2") (pintype "passive"))
      (node (ref "R_LED_4") (pin "2") (pinfunction "2_2") (pintype "passive"))
      (node (ref "R_LED_5") (pin "2") (pinfunction "2_2") (pintype "passive"))
      (node (ref "R_LED_6") (pin "2") (pinfunction "2_2") (pintype "passive"))
      (node (ref "R_LED_7") (pin "2") (pinfunction "2_2") (pintype "passive"))
      (node (ref "R_LED_8") (pin "2") (pinfunction "2_2") (pintype "passive"))
      (node (ref "SW1") (pin "4") (pinfunction "P4_4") (pintype "passive"))
      (node (ref "Siwa_receiver_1") (pin "8") (pinfunction "Pin8_8") (pintype "passive"))
      (node (ref "Siwa_receiver_2") (pin "1") (pinfunction "Pin1_1") (pintype "passive"))
      (node (ref "Siwa_receiver_3") (pin "1") (pinfunction "Pin1_1") (pintype "passive"))
      (node (ref "Siwa_receiver_4") (pin "1") (pinfunction "Pin1_1") (pintype "passive"))
    )
    (net (code "9") (name "GPIO_LED_0") (class "Default")
      (node (ref "HEADER_20x2") (pin "25") (pinfunction "25_25") (pintype "passive"))
      (node (ref "LED1") (pin "2") (pinfunction "A_2") (pintype "passive"))
    )
    (net (code "10") (name "GPIO_LED_1") (class "Default")
      (node (ref "HEADER_20x2") (pin "27") (pinfunction "27_27") (pintype "passive"))
      (node (ref "LED2") (pin "2") (pinfunction "A_2") (pintype "passive"))
    )
    (net (code "11") (name "GPIO_LED_2") (class "Default")
      (node (ref "HEADER_20x2") (pin "29") (pinfunction "29_29") (pintype "passive"))
      (node (ref "LED3") (pin "2") (pinfunction "A_2") (pintype "passive"))
    )
    (net (code "12") (name "GPIO_LED_3") (class "Default")
      (node (ref "HEADER_20x2") (pin "31") (pinfunction "31_31") (pintype "passive"))
      (node (ref "LED4") (pin "2") (pinfunction "A_2") (pintype "passive"))
    )
    (net (code "13") (name "GPIO_LED_4") (class "Default")
      (node (ref "HEADER_20x2") (pin "33") (pinfunction "33_33") (pintype "passive"))
      (node (ref "LED5") (pin "2") (pinfunction "A_2") (pintype "passive"))
    )
    (net (code "14") (name "GPIO_LED_5") (class "Default")
      (node (ref "HEADER_20x2") (pin "35") (pinfunction "35_35") (pintype "passive"))
      (node (ref "LED6") (pin "2") (pinfunction "A_2") (pintype "passive"))
    )
    (net (code "15") (name "GPIO_LED_6") (class "Default")
      (node (ref "HEADER_20x2") (pin "37") (pinfunction "37_37") (pintype "passive"))
      (node (ref "LED7") (pin "2") (pinfunction "A_2") (pintype "passive"))
    )
    (net (code "16") (name "GPIO_LED_7") (class "Default")
      (node (ref "HEADER_20x2") (pin "39") (pinfunction "39_39") (pintype "passive"))
      (node (ref "LED8") (pin "2") (pinfunction "A_2") (pintype "passive"))
    )
    (net (code "17") (name "GPIO_PAD_0") (class "Default")
      (node (ref "HEADER_20x2") (pin "10") (pinfunction "10_10") (pintype "passive"))
      (node (ref "Siwa_receiver_1") (pin "7") (pinfunction "Pin7_7") (pintype "passive"))
    )
    (net (code "18") (name "GPIO_PAD_0_OUT") (class "Default")
      (node (ref "HEADER_20x2") (pin "9") (pinfunction "9_9") (pintype "passive"))
      (node (ref "LS_1") (pin "4") (pinfunction "SDA_A_4") (pintype "bidirectional"))
    )
    (net (code "19") (name "GPIO_PAD_1") (class "Default")
      (node (ref "HEADER_20x2") (pin "12") (pinfunction "12_12") (pintype "passive"))
      (node (ref "Siwa_receiver_1") (pin "6") (pinfunction "Pin6_6") (pintype "passive"))
    )
    (net (code "20") (name "GPIO_PAD_1_OUT") (class "Default")
      (node (ref "HEADER_20x2") (pin "11") (pinfunction "11_11") (pintype "passive"))
      (node (ref "LS_1") (pin "5") (pinfunction "SCL_A_5") (pintype "bidirectional"))
    )
    (net (code "21") (name "GPIO_PAD_2") (class "Default")
      (node (ref "HEADER_20x2") (pin "14") (pinfunction "14_14") (pintype "passive"))
      (node (ref "Siwa_receiver_1") (pin "4") (pinfunction "Pin4_4") (pintype "passive"))
    )
    (net (code "22") (name "GPIO_PAD_2_OUT") (class "Default")
      (node (ref "HEADER_20x2") (pin "13") (pinfunction "13_13") (pintype "passive"))
      (node (ref "LS_2") (pin "4") (pinfunction "SDA_A_4") (pintype "bidirectional"))
    )
    (net (code "23") (name "GPIO_PAD_3") (class "Default")
      (node (ref "HEADER_20x2") (pin "16") (pinfunction "16_16") (pintype "passive"))
      (node (ref "Siwa_receiver_1") (pin "1") (pinfunction "Pin1_1") (pintype "passive"))
    )
    (net (code "24") (name "GPIO_PAD_3_OUT") (class "Default")
      (node (ref "HEADER_20x2") (pin "15") (pinfunction "15_15") (pintype "passive"))
      (node (ref "LS_2") (pin "5") (pinfunction "SCL_A_5") (pintype "bidirectional"))
    )
    (net (code "25") (name "GPIO_PAD_4") (class "Default")
      (node (ref "HEADER_20x2") (pin "18") (pinfunction "18_18") (pintype "passive"))
      (node (ref "Siwa_receiver_3") (pin "2") (pinfunction "Pin2_2") (pintype "passive"))
    )
    (net (code "26") (name "GPIO_PAD_4_OUT") (class "Default")
      (node (ref "HEADER_20x2") (pin "17") (pinfunction "17_17") (pintype "passive"))
      (node (ref "LS_3") (pin "5") (pinfunction "SCL_A_5") (pintype "bidirectional"))
    )
    (net (code "27") (name "GPIO_PAD_5") (class "Default")
      (node (ref "HEADER_20x2") (pin "20") (pinfunction "20_20") (pintype "passive"))
      (node (ref "Siwa_receiver_3") (pin "3") (pinfunction "Pin3_3") (pintype "passive"))
    )
    (net (code "28") (name "GPIO_PAD_5_OUT") (class "Default")
      (node (ref "HEADER_20x2") (pin "19") (pinfunction "19_19") (pintype "passive"))
      (node (ref "LS_3") (pin "4") (pinfunction "SDA_A_4") (pintype "bidirectional"))
    )
    (net (code "29") (name "GPIO_PAD_6") (class "Default")
      (node (ref "HEADER_20x2") (pin "22") (pinfunction "22_22") (pintype "passive"))
      (node (ref "Siwa_receiver_3") (pin "5") (pinfunction "Pin5_5") (pintype "passive"))
    )
    (net (code "30") (name "GPIO_PAD_6_OUT") (class "Default")
      (node (ref "HEADER_20x2") (pin "21") (pinfunction "21_21") (pintype "passive"))
      (node (ref "LS_4") (pin "5") (pinfunction "SCL_A_5") (pintype "bidirectional"))
    )
    (net (code "31") (name "GPIO_PAD_7") (class "Default")
      (node (ref "HEADER_20x2") (pin "24") (pinfunction "24_24") (pintype "passive"))
      (node (ref "Siwa_receiver_3") (pin "8") (pinfunction "Pin8_8") (pintype "passive"))
    )
    (net (code "32") (name "GPIO_PAD_7_OUT") (class "Default")
      (node (ref "HEADER_20x2") (pin "23") (pinfunction "23_23") (pintype "passive"))
      (node (ref "LS_4") (pin "4") (pinfunction "SDA_A_4") (pintype "bidirectional"))
    )
    (net (code "33") (name "H_LED_4") (class "Default")
      (node (ref "GPIO_BUFFER_LED_3") (pin "6") (pinfunction "1Y_6") (pintype "passive"))
      (node (ref "HEADER_20x2") (pin "34") (pinfunction "34_34") (pintype "passive"))
    )
    (net (code "34") (name "H_LED_5") (class "Default")
      (node (ref "GPIO_BUFFER_LED_3") (pin "4") (pinfunction "2Y_4") (pintype "passive"))
      (node (ref "HEADER_20x2") (pin "36") (pinfunction "36_36") (pintype "passive"))
    )
    (net (code "35") (name "H_LED_6") (class "Default")
      (node (ref "GPIO_BUFFER_LED_4") (pin "6") (pinfunction "1Y_6") (pintype "passive"))
      (node (ref "HEADER_20x2") (pin "38") (pinfunction "38_38") (pintype "passive"))
    )
    (net (code "36") (name "H_LED_7") (class "Default")
      (node (ref "GPIO_BUFFER_LED_4") (pin "4") (pinfunction "2Y_4") (pintype "passive"))
      (node (ref "HEADER_20x2") (pin "40") (pinfunction "40_40") (pintype "passive"))
    )
    (net (code "37") (name "MAIP") (class "Default")
      (node (ref "No_needed_signals") (pin "3") (pinfunction "3_3") (pintype "passive"))
      (node (ref "Siwa_receiver_4") (pin "5") (pinfunction "Pin5_5") (pintype "passive"))
    )
    (net (code "38") (name "Net-(1.0_V_REGULATOR-NR)") (class "Default")
      (node (ref "1.0_V_REGULATOR") (pin "4") (pinfunction "NR_4") (pintype "passive"))
      (node (ref "C_NR1") (pin "2") (pinfunction "2_2") (pintype "passive"))
    )
    (net (code "39") (name "Net-(1.8_V_REGULATOR-BP)") (class "Default")
      (node (ref "1.8_V_REGULATOR") (pin "4") (pinfunction "BP_4") (pintype "passive"))
      (node (ref "C_BP1") (pin "1") (pinfunction "1_1") (pintype "passive"))
    )
    (net (code "40") (name "Net-(3.0_V_REGULATOR-BP)") (class "Default")
      (node (ref "3.0_V_REGULATOR") (pin "4") (pinfunction "BP_4") (pintype "passive"))
      (node (ref "C_BP2") (pin "1") (pinfunction "1_1") (pintype "passive"))
    )
    (net (code "41") (name "Net-(CLK_BUFFER-CLK0)") (class "Default")
      (node (ref "CLK_BUFFER") (pin "4") (pinfunction "CLK0_4") (pintype "input"))
      (node (ref "R_CLK1") (pin "1") (pinfunction "1_1") (pintype "passive"))
    )
    (net (code "42") (name "Net-(CLK_BUFFER-FIN)") (class "Default")
      (node (ref "CLK_BUFFER") (pin "3") (pinfunction "FIN_3") (pintype "input"))
      (node (ref "OSCILLATOR_20MHz") (pin "3") (pinfunction "Output_3") (pintype "output"))
    )
    (net (code "43") (name "Net-(GPIOS_DISPLAY-Pad1)") (class "Default")
      (node (ref "GPIOS_DISPLAY") (pin "1") (pinfunction "1_1") (pintype "passive"))
      (node (ref "OLED_SCREEN_BASE") (pin "5") (pinfunction "5_5") (pintype "passive"))
    )
    (net (code "44") (name "Net-(GPIOS_DISPLAY-Pad3)") (class "Default")
      (node (ref "GPIOS_DISPLAY") (pin "3") (pinfunction "3_3") (pintype "passive"))
      (node (ref "OLED_SCREEN_BASE") (pin "6") (pinfunction "6_6") (pintype "passive"))
    )
    (net (code "45") (name "Net-(GPIOS_DISPLAY-Pad5)") (class "Default")
      (node (ref "GPIOS_DISPLAY") (pin "5") (pinfunction "5_5") (pintype "passive"))
      (node (ref "OLED_SCREEN_BASE") (pin "7") (pinfunction "7_7") (pintype "passive"))
    )
    (net (code "46") (name "Net-(GPIOS_DISPLAY-Pad7)") (class "Default")
      (node (ref "GPIOS_DISPLAY") (pin "7") (pinfunction "7_7") (pintype "passive"))
      (node (ref "OLED_SCREEN_BASE") (pin "4") (pinfunction "4_4") (pintype "passive"))
    )
    (net (code "47") (name "Net-(GPIO_BUFFER1-1A)") (class "Default")
      (node (ref "GPIOS_LEDs_0") (pin "4") (pinfunction "4_4") (pintype "passive"))
      (node (ref "GPIO_BUFFER1") (pin "1") (pinfunction "1A_1") (pintype "passive"))
      (node (ref "LS_OUT_1") (pin "5") (pinfunction "5_5") (pintype "passive"))
    )
    (net (code "48") (name "Net-(GPIO_BUFFER1-1Y)") (class "Default")
      (node (ref "GPIOS_DISPLAY") (pin "6") (pinfunction "6_6") (pintype "passive"))
      (node (ref "GPIO_BUFFER1") (pin "6") (pinfunction "1Y_6") (pintype "passive"))
    )
    (net (code "49") (name "Net-(GPIO_BUFFER1-2A)") (class "Default")
      (node (ref "GPIOS_LEDs_0") (pin "2") (pinfunction "2_2") (pintype "passive"))
      (node (ref "GPIO_BUFFER1") (pin "3") (pinfunction "2A_3") (pintype "passive"))
      (node (ref "LS_OUT_1") (pin "7") (pinfunction "7_7") (pintype "passive"))
    )
    (net (code "50") (name "Net-(GPIO_BUFFER1-2Y)") (class "Default")
      (node (ref "GPIOS_DISPLAY") (pin "8") (pinfunction "8_8") (pintype "passive"))
      (node (ref "GPIO_BUFFER1") (pin "4") (pinfunction "2Y_4") (pintype "passive"))
    )
    (net (code "51") (name "Net-(GPIO_BUFFER2-1A)") (class "Default")
      (node (ref "GPIOS_LEDs_0") (pin "8") (pinfunction "8_8") (pintype "passive"))
      (node (ref "GPIO_BUFFER2") (pin "1") (pinfunction "1A_1") (pintype "passive"))
      (node (ref "LS_OUT_1") (pin "1") (pinfunction "1_1") (pintype "passive"))
    )
    (net (code "52") (name "Net-(GPIO_BUFFER2-1Y)") (class "Default")
      (node (ref "GPIOS_DISPLAY") (pin "2") (pinfunction "2_2") (pintype "passive"))
      (node (ref "GPIO_BUFFER2") (pin "6") (pinfunction "1Y_6") (pintype "passive"))
    )
    (net (code "53") (name "Net-(GPIO_BUFFER2-2A)") (class "Default")
      (node (ref "GPIOS_LEDs_0") (pin "6") (pinfunction "6_6") (pintype "passive"))
      (node (ref "GPIO_BUFFER2") (pin "3") (pinfunction "2A_3") (pintype "passive"))
      (node (ref "LS_OUT_1") (pin "3") (pinfunction "3_3") (pintype "passive"))
    )
    (net (code "54") (name "Net-(GPIO_BUFFER2-2Y)") (class "Default")
      (node (ref "GPIOS_DISPLAY") (pin "4") (pinfunction "4_4") (pintype "passive"))
      (node (ref "GPIO_BUFFER2") (pin "4") (pinfunction "2Y_4") (pintype "passive"))
    )
    (net (code "55") (name "Net-(GPIO_BUFFER_LED_1-1A)") (class "Default")
      (node (ref "GPIOS_LEDs_0") (pin "1") (pinfunction "1_1") (pintype "passive"))
      (node (ref "GPIO_BUFFER_LED_1") (pin "1") (pinfunction "1A_1") (pintype "passive"))
    )
    (net (code "56") (name "Net-(GPIO_BUFFER_LED_1-1Y)") (class "Default")
      (node (ref "GPIO_BUFFER_LED_1") (pin "6") (pinfunction "1Y_6") (pintype "passive"))
      (node (ref "HEADER_20x2") (pin "26") (pinfunction "26_26") (pintype "passive"))
    )
    (net (code "57") (name "Net-(GPIO_BUFFER_LED_1-2A)") (class "Default")
      (node (ref "GPIOS_LEDs_0") (pin "3") (pinfunction "3_3") (pintype "passive"))
      (node (ref "GPIO_BUFFER_LED_1") (pin "3") (pinfunction "2A_3") (pintype "passive"))
    )
    (net (code "58") (name "Net-(GPIO_BUFFER_LED_1-2Y)") (class "Default")
      (node (ref "GPIO_BUFFER_LED_1") (pin "4") (pinfunction "2Y_4") (pintype "passive"))
      (node (ref "HEADER_20x2") (pin "28") (pinfunction "28_28") (pintype "passive"))
    )
    (net (code "59") (name "Net-(GPIO_BUFFER_LED_2-1A)") (class "Default")
      (node (ref "GPIOS_LEDs_0") (pin "5") (pinfunction "5_5") (pintype "passive"))
      (node (ref "GPIO_BUFFER_LED_2") (pin "1") (pinfunction "1A_1") (pintype "passive"))
    )
    (net (code "60") (name "Net-(GPIO_BUFFER_LED_2-1Y)") (class "Default")
      (node (ref "GPIO_BUFFER_LED_2") (pin "6") (pinfunction "1Y_6") (pintype "passive"))
      (node (ref "HEADER_20x2") (pin "30") (pinfunction "30_30") (pintype "passive"))
    )
    (net (code "61") (name "Net-(GPIO_BUFFER_LED_2-2A)") (class "Default")
      (node (ref "GPIOS_LEDs_0") (pin "7") (pinfunction "7_7") (pintype "passive"))
      (node (ref "GPIO_BUFFER_LED_2") (pin "3") (pinfunction "2A_3") (pintype "passive"))
    )
    (net (code "62") (name "Net-(GPIO_BUFFER_LED_2-2Y)") (class "Default")
      (node (ref "GPIO_BUFFER_LED_2") (pin "4") (pinfunction "2Y_4") (pintype "passive"))
      (node (ref "HEADER_20x2") (pin "32") (pinfunction "32_32") (pintype "passive"))
    )
    (net (code "63") (name "Net-(GPIO_BUFFER_LED_3-1A)") (class "Default")
      (node (ref "GPIO_BUFFER_LED_3") (pin "1") (pinfunction "1A_1") (pintype "passive"))
      (node (ref "LS_OUT_2") (pin "1") (pinfunction "1_1") (pintype "passive"))
    )
    (net (code "64") (name "Net-(GPIO_BUFFER_LED_3-2A)") (class "Default")
      (node (ref "GPIO_BUFFER_LED_3") (pin "3") (pinfunction "2A_3") (pintype "passive"))
      (node (ref "LS_OUT_2") (pin "3") (pinfunction "3_3") (pintype "passive"))
    )
    (net (code "65") (name "Net-(GPIO_BUFFER_LED_4-1A)") (class "Default")
      (node (ref "GPIO_BUFFER_LED_4") (pin "1") (pinfunction "1A_1") (pintype "passive"))
      (node (ref "LS_OUT_2") (pin "5") (pinfunction "5_5") (pintype "passive"))
    )
    (net (code "66") (name "Net-(GPIO_BUFFER_LED_4-2A)") (class "Default")
      (node (ref "GPIO_BUFFER_LED_4") (pin "3") (pinfunction "2A_3") (pintype "passive"))
      (node (ref "LS_OUT_2") (pin "7") (pinfunction "7_7") (pintype "passive"))
    )
    (net (code "67") (name "Net-(HEADER_20x2-Pad2)") (class "Default")
      (node (ref "HEADER_20x2") (pin "2") (pinfunction "2_2") (pintype "passive"))
      (node (ref "R_CLK1") (pin "2") (pinfunction "2_2") (pintype "passive"))
    )
    (net (code "68") (name "Net-(LED1-K)") (class "Default")
      (node (ref "LED1") (pin "1") (pinfunction "K_1") (pintype "passive"))
      (node (ref "R_LED_1") (pin "1") (pinfunction "1_1") (pintype "passive"))
    )
    (net (code "69") (name "Net-(LED2-K)") (class "Default")
      (node (ref "LED2") (pin "1") (pinfunction "K_1") (pintype "passive"))
      (node (ref "R_LED_2") (pin "1") (pinfunction "1_1") (pintype "passive"))
    )
    (net (code "70") (name "Net-(LED3-K)") (class "Default")
      (node (ref "LED3") (pin "1") (pinfunction "K_1") (pintype "passive"))
      (node (ref "R_LED_3") (pin "1") (pinfunction "1_1") (pintype "passive"))
    )
    (net (code "71") (name "Net-(LED4-K)") (class "Default")
      (node (ref "LED4") (pin "1") (pinfunction "K_1") (pintype "passive"))
      (node (ref "R_LED_4") (pin "1") (pinfunction "1_1") (pintype "passive"))
    )
    (net (code "72") (name "Net-(LED5-K)") (class "Default")
      (node (ref "LED5") (pin "1") (pinfunction "K_1") (pintype "passive"))
      (node (ref "R_LED_5") (pin "1") (pinfunction "1_1") (pintype "passive"))
    )
    (net (code "73") (name "Net-(LED6-K)") (class "Default")
      (node (ref "LED6") (pin "1") (pinfunction "K_1") (pintype "passive"))
      (node (ref "R_LED_6") (pin "1") (pinfunction "1_1") (pintype "passive"))
    )
    (net (code "74") (name "Net-(LED7-K)") (class "Default")
      (node (ref "LED7") (pin "1") (pinfunction "K_1") (pintype "passive"))
      (node (ref "R_LED_7") (pin "1") (pinfunction "1_1") (pintype "passive"))
    )
    (net (code "75") (name "Net-(LED8-K)") (class "Default")
      (node (ref "LED8") (pin "1") (pinfunction "K_1") (pintype "passive"))
      (node (ref "R_LED_8") (pin "1") (pinfunction "1_1") (pintype "passive"))
    )
    (net (code "76") (name "Net-(LS_1-SCL_B)") (class "Default")
      (node (ref "LS_1") (pin "8") (pinfunction "SCL_B_8") (pintype "bidirectional"))
      (node (ref "LS_OUT_1") (pin "6") (pinfunction "6_6") (pintype "passive"))
    )
    (net (code "77") (name "Net-(LS_1-SDA_B)") (class "Default")
      (node (ref "LS_1") (pin "1") (pinfunction "SDA_B_1") (pintype "bidirectional"))
      (node (ref "LS_OUT_1") (pin "8") (pinfunction "8_8") (pintype "passive"))
    )
    (net (code "78") (name "Net-(LS_2-SCL_B)") (class "Default")
      (node (ref "LS_2") (pin "8") (pinfunction "SCL_B_8") (pintype "bidirectional"))
      (node (ref "LS_OUT_1") (pin "2") (pinfunction "2_2") (pintype "passive"))
    )
    (net (code "79") (name "Net-(LS_2-SDA_B)") (class "Default")
      (node (ref "LS_2") (pin "1") (pinfunction "SDA_B_1") (pintype "bidirectional"))
      (node (ref "LS_OUT_1") (pin "4") (pinfunction "4_4") (pintype "passive"))
    )
    (net (code "80") (name "Net-(LS_3-SCL_B)") (class "Default")
      (node (ref "LS_3") (pin "8") (pinfunction "SCL_B_8") (pintype "bidirectional"))
      (node (ref "LS_OUT_2") (pin "2") (pinfunction "2_2") (pintype "passive"))
    )
    (net (code "81") (name "Net-(LS_3-SDA_B)") (class "Default")
      (node (ref "LS_3") (pin "1") (pinfunction "SDA_B_1") (pintype "bidirectional"))
      (node (ref "LS_OUT_2") (pin "4") (pinfunction "4_4") (pintype "passive"))
    )
    (net (code "82") (name "Net-(LS_4-SCL_B)") (class "Default")
      (node (ref "LS_4") (pin "8") (pinfunction "SCL_B_8") (pintype "bidirectional"))
      (node (ref "LS_OUT_2") (pin "6") (pinfunction "6_6") (pintype "passive"))
    )
    (net (code "83") (name "Net-(LS_4-SDA_B)") (class "Default")
      (node (ref "LS_4") (pin "1") (pinfunction "SDA_B_1") (pintype "bidirectional"))
      (node (ref "LS_OUT_2") (pin "8") (pinfunction "8_8") (pintype "passive"))
    )
    (net (code "84") (name "Net-(RESET_BUFFER-1A)") (class "Default")
      (node (ref "RESET_BUFFER") (pin "1") (pinfunction "1A_1") (pintype "passive"))
      (node (ref "RESET_CIRCUIT") (pin "2") (pinfunction "RESET_2") (pintype "passive"))
    )
    (net (code "85") (name "Net-(RESET_BUFFER-1Y)") (class "Default")
      (node (ref "HEADER_20x2") (pin "6") (pinfunction "6_6") (pintype "passive"))
      (node (ref "RESET_BUFFER") (pin "6") (pinfunction "1Y_6") (pintype "passive"))
    )
    (net (code "86") (name "Net-(RESET_CIRCUIT-~{MR})") (class "Default")
      (node (ref "RESET_CIRCUIT") (pin "3") (pinfunction "~{MR}_3") (pintype "passive"))
      (node (ref "SW1") (pin "2") (pinfunction "P2_2") (pintype "passive"))
    )
    (net (code "87") (name "Net-(Siwa_receiver_2-Pin6)") (class "Default")
      (node (ref "MEMORY_CONNECTOR") (pin "6") (pinfunction "6_6") (pintype "passive"))
      (node (ref "Siwa_receiver_2") (pin "6") (pinfunction "Pin6_6") (pintype "passive"))
    )
    (net (code "88") (name "Net-(Siwa_receiver_2-Pin7)") (class "Default")
      (node (ref "MEMORY_CONNECTOR") (pin "5") (pinfunction "5_5") (pintype "passive"))
      (node (ref "Siwa_receiver_2") (pin "7") (pinfunction "Pin7_7") (pintype "passive"))
    )
    (net (code "89") (name "Net-(Siwa_receiver_2-Pin8)") (class "Default")
      (node (ref "MEMORY_CONNECTOR") (pin "2") (pinfunction "2_2") (pintype "passive"))
      (node (ref "Siwa_receiver_2") (pin "8") (pinfunction "Pin8_8") (pintype "passive"))
    )
    (net (code "90") (name "Net-(Siwa_receiver_4-Pin3)") (class "Default")
      (node (ref "HEADER_20x2") (pin "1") (pinfunction "1_1") (pintype "passive"))
      (node (ref "HEADER_20x2") (pin "3") (pinfunction "3_3") (pintype "passive"))
      (node (ref "Siwa_receiver_4") (pin "3") (pinfunction "Pin3_3") (pintype "passive"))
    )
    (net (code "91") (name "Net-(Siwa_receiver_4-Pin6)") (class "Default")
      (node (ref "HEADER_20x2") (pin "5") (pinfunction "5_5") (pintype "passive"))
      (node (ref "HEADER_20x2") (pin "7") (pinfunction "7_7") (pintype "passive"))
      (node (ref "Siwa_receiver_4") (pin "6") (pinfunction "Pin6_6") (pintype "passive"))
    )
    (net (code "92") (name "Net-(Siwa_receiver_4-Pin8)") (class "Default")
      (node (ref "MEMORY_CONNECTOR") (pin "1") (pinfunction "1_1") (pintype "passive"))
      (node (ref "Siwa_receiver_4") (pin "8") (pinfunction "Pin8_8") (pintype "passive"))
    )
    (net (code "93") (name "POC_CONTROL") (class "Default")
      (node (ref "No_needed_signals") (pin "1") (pinfunction "1_1") (pintype "passive"))
      (node (ref "Siwa_receiver_4") (pin "4") (pinfunction "Pin4_4") (pintype "passive"))
    )
    (net (code "94") (name "UART_RX") (class "Default")
      (node (ref "No_needed_signals") (pin "7") (pinfunction "7_7") (pintype "passive"))
      (node (ref "Siwa_receiver_2") (pin "4") (pinfunction "Pin4_4") (pintype "passive"))
    )
    (net (code "95") (name "UART_TX") (class "Default")
      (node (ref "No_needed_signals") (pin "5") (pinfunction "5_5") (pintype "passive"))
      (node (ref "Siwa_receiver_2") (pin "2") (pinfunction "Pin2_2") (pintype "passive"))
    )
    (net (code "96") (name "unconnected-(HEADER_20x2-4-Pad4{slash}EXTERNAL_CLK)") (class "Default")
      (node (ref "HEADER_20x2") (pin "4/EXTERNAL_CLK") (pinfunction "4_4/EXTERNAL_CLK") (pintype "passive"))
    )
    (net (code "97") (name "unconnected-(HEADER_20x2-8-Pad8{slash}EXTERNAL_RESET)") (class "Default")
      (node (ref "HEADER_20x2") (pin "8/EXTERNAL_RESET") (pinfunction "8_8/EXTERNAL_RESET") (pintype "passive"))
    )
    (net (code "98") (name "unconnected-(OLED_SCREEN_BASE-Pad8)") (class "Default")
      (node (ref "OLED_SCREEN_BASE") (pin "8") (pinfunction "8_8") (pintype "passive"))
    )
    (net (code "99") (name "unconnected-(RESET_BUFFER-2A-Pad3)") (class "Default")
      (node (ref "RESET_BUFFER") (pin "3") (pinfunction "2A_3") (pintype "passive"))
    )
    (net (code "100") (name "unconnected-(RESET_BUFFER-2Y-Pad4)") (class "Default")
      (node (ref "RESET_BUFFER") (pin "4") (pinfunction "2Y_4") (pintype "passive"))
    )
    (net (code "101") (name "unconnected-(SW1-P1-Pad1)") (class "Default")
      (node (ref "SW1") (pin "1") (pinfunction "P1_1") (pintype "passive"))
    )
    (net (code "102") (name "unconnected-(SW1-P3-Pad3)") (class "Default")
      (node (ref "SW1") (pin "3") (pinfunction "P3_3") (pintype "passive"))
    )
  )
)
